# LEDRing.net
KiCad netlist of a schematic drawn in Altium Designer
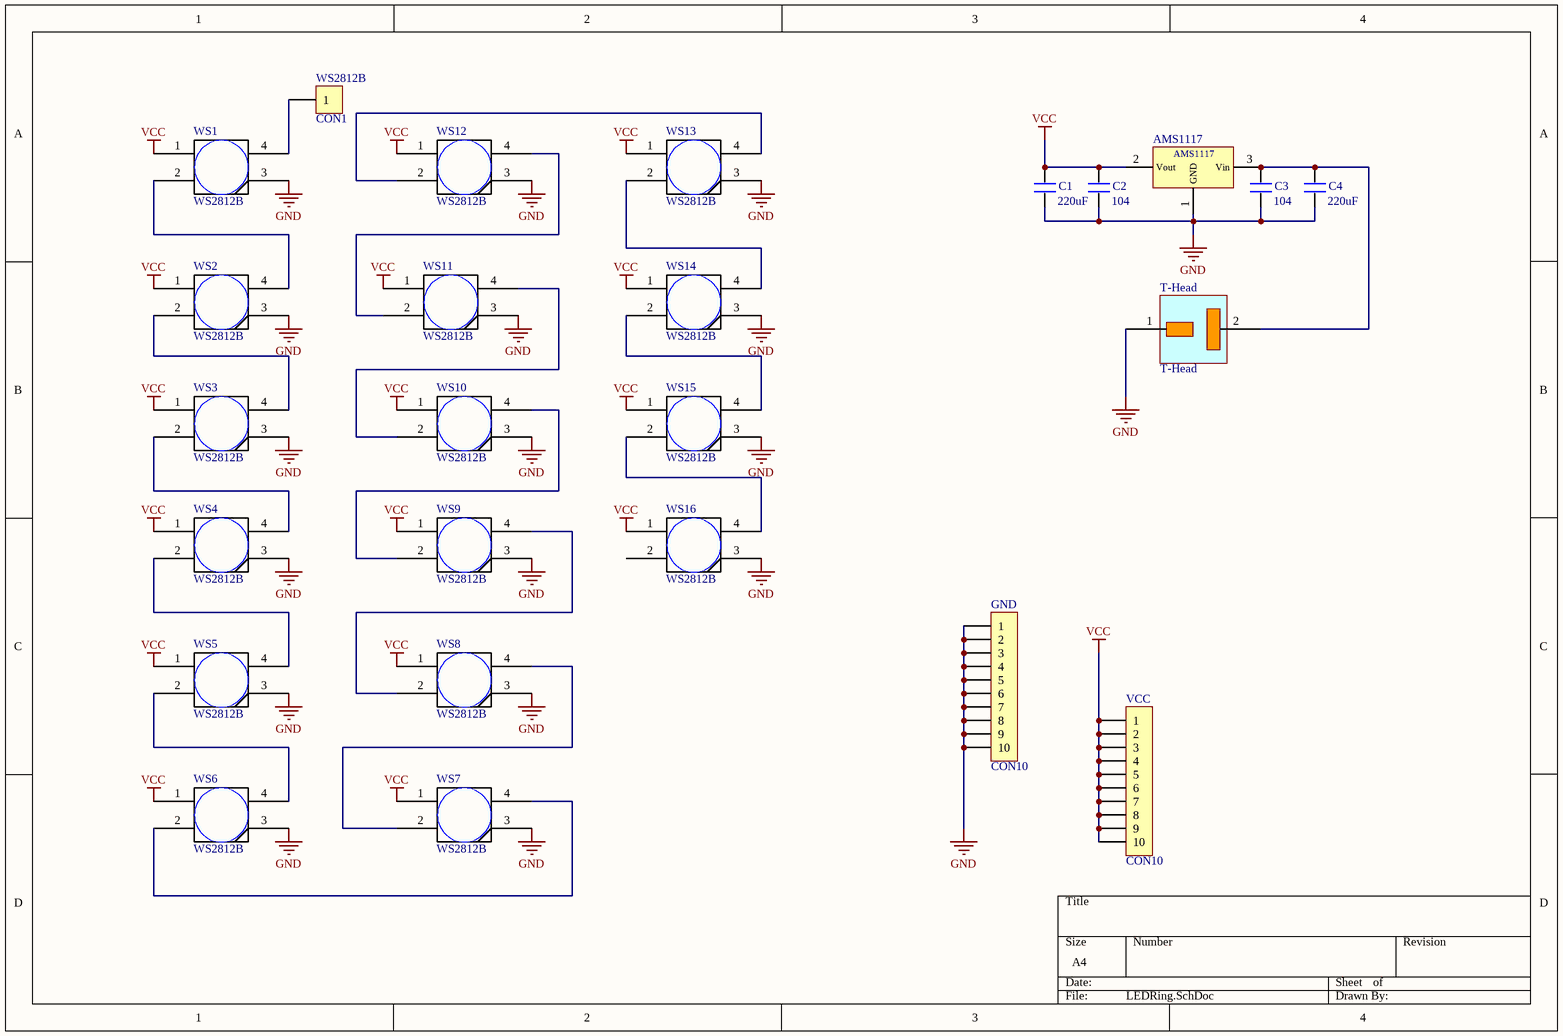
[diagram p0: LEDRing.SchDoc]

(export (version "E")
  (design (tool "Eeschema 10.0.6"))
  (components
    (comp (ref "AMS1117")
      (value "AMS1117")
      (footprint "AMS1117-3.3")
      (libsource (lib "WS2812") (part "AMS1117"))
    )
    (comp (ref "C1") (value "220uF") (footprint "0805") (libsource (lib "MiniFly V1.32") (part "C")))
    (comp (ref "C2") (value "104") (footprint "0805") (libsource (lib "MiniFly V1.32") (part "C")))
    (comp (ref "C3") (value "104") (footprint "0805") (libsource (lib "MiniFly V1.32") (part "C")))
    (comp (ref "C4") (value "220uF") (footprint "0805") (libsource (lib "MiniFly V1.32") (part "C")))
    (comp (ref "GND") (value "CON10") (footprint "HDR1X10") (libsource (lib "常用元件库") (part "CON10")))
    (comp (ref "T-Head") (value "T-Head") (footprint "T_head") (libsource (lib "WS2812") (part "T-Head")))
    (comp (ref "VCC") (value "CON10") (footprint "HDR1X10") (libsource (lib "常用元件库") (part "CON10")))
    (comp (ref "WS1") (value "WS2812B") (footprint "WS2812B") (libsource (lib "WS2812") (part "Component_1")))
    (comp (ref "WS2") (value "WS2812B") (footprint "WS2812B") (libsource (lib "WS2812") (part "Component_1")))
    (comp (ref "WS3") (value "WS2812B") (footprint "WS2812B") (libsource (lib "WS2812") (part "Component_1")))
    (comp (ref "WS4") (value "WS2812B") (footprint "WS2812B") (libsource (lib "WS2812") (part "Component_1")))
    (comp (ref "WS5") (value "WS2812B") (footprint "WS2812B") (libsource (lib "WS2812") (part "Component_1")))
    (comp (ref "WS6") (value "WS2812B") (footprint "WS2812B") (libsource (lib "WS2812") (part "Component_1")))
    (comp (ref "WS7") (value "WS2812B") (footprint "WS2812B") (libsource (lib "WS2812") (part "Component_1")))
    (comp (ref "WS8") (value "WS2812B") (footprint "WS2812B") (libsource (lib "WS2812") (part "Component_1")))
    (comp (ref "WS9") (value "WS2812B") (footprint "WS2812B") (libsource (lib "WS2812") (part "Component_1")))
    (comp (ref "WS10")
      (value "WS2812B")
      (footprint "WS2812B")
      (libsource (lib "WS2812") (part "Component_1"))
    )
    (comp (ref "WS11")
      (value "WS2812B")
      (footprint "WS2812B")
      (libsource (lib "WS2812") (part "Component_1"))
    )
    (comp (ref "WS12")
      (value "WS2812B")
      (footprint "WS2812B")
      (libsource (lib "WS2812") (part "Component_1"))
    )
    (comp (ref "WS13")
      (value "WS2812B")
      (footprint "WS2812B")
      (libsource (lib "WS2812") (part "Component_1"))
    )
    (comp (ref "WS14")
      (value "WS2812B")
      (footprint "WS2812B")
      (libsource (lib "WS2812") (part "Component_1"))
    )
    (comp (ref "WS15")
      (value "WS2812B")
      (footprint "WS2812B")
      (libsource (lib "WS2812") (part "Component_1"))
    )
    (comp (ref "WS16")
      (value "WS2812B")
      (footprint "WS2812B")
      (libsource (lib "WS2812") (part "Component_1"))
    )
    (comp (ref "WS2812B") (value "CON1") (footprint "PIN1") (libsource (lib "常用元件库") (part "CON1")))
  )
  (nets
    (net (code "1") (name "GND") (class "Default")
      (node (ref "AMS1117") (pin "1") (pinfunction "GND_1") (pintype "passive"))
      (node (ref "C1") (pin "1") (pintype "passive"))
      (node (ref "C2") (pin "1") (pintype "passive"))
      (node (ref "C3") (pin "1") (pintype "passive"))
      (node (ref "C4") (pin "1") (pintype "passive"))
      (node (ref "GND") (pin "1") (pinfunction "1_1") (pintype "passive"))
      (node (ref "GND") (pin "10") (pinfunction "10_10") (pintype "passive"))
      (node (ref "GND") (pin "2") (pinfunction "2_2") (pintype "passive"))
      (node (ref "GND") (pin "3") (pinfunction "3_3") (pintype "passive"))
      (node (ref "GND") (pin "4") (pinfunction "4_4") (pintype "passive"))
      (node (ref "GND") (pin "5") (pinfunction "5_5") (pintype "passive"))
      (node (ref "GND") (pin "6") (pinfunction "6_6") (pintype "passive"))
      (node (ref "GND") (pin "7") (pinfunction "7_7") (pintype "passive"))
      (node (ref "GND") (pin "8") (pinfunction "8_8") (pintype "passive"))
      (node (ref "GND") (pin "9") (pinfunction "9_9") (pintype "passive"))
      (node (ref "T-Head") (pin "1") (pinfunction "GND_1") (pintype "passive"))
      (node (ref "WS1") (pin "3") (pinfunction "GND_3") (pintype "passive"))
      (node (ref "WS10") (pin "3") (pinfunction "GND_3") (pintype "passive"))
      (node (ref "WS11") (pin "3") (pinfunction "GND_3") (pintype "passive"))
      (node (ref "WS12") (pin "3") (pinfunction "GND_3") (pintype "passive"))
      (node (ref "WS13") (pin "3") (pinfunction "GND_3") (pintype "passive"))
      (node (ref "WS14") (pin "3") (pinfunction "GND_3") (pintype "passive"))
      (node (ref "WS15") (pin "3") (pinfunction "GND_3") (pintype "passive"))
      (node (ref "WS16") (pin "3") (pinfunction "GND_3") (pintype "passive"))
      (node (ref "WS2") (pin "3") (pinfunction "GND_3") (pintype "passive"))
      (node (ref "WS3") (pin "3") (pinfunction "GND_3") (pintype "passive"))
      (node (ref "WS4") (pin "3") (pinfunction "GND_3") (pintype "passive"))
      (node (ref "WS5") (pin "3") (pinfunction "GND_3") (pintype "passive"))
      (node (ref "WS6") (pin "3") (pinfunction "GND_3") (pintype "passive"))
      (node (ref "WS7") (pin "3") (pinfunction "GND_3") (pintype "passive"))
      (node (ref "WS8") (pin "3") (pinfunction "GND_3") (pintype "passive"))
      (node (ref "WS9") (pin "3") (pinfunction "GND_3") (pintype "passive"))
    )
    (net (code "2") (name "Net-(AMS1117-Vin)") (class "Default")
      (node (ref "AMS1117") (pin "3") (pinfunction "Vin_3") (pintype "passive"))
      (node (ref "C3") (pin "2") (pintype "passive"))
      (node (ref "C4") (pin "2") (pintype "passive"))
      (node (ref "T-Head") (pin "2") (pinfunction "VCC_2") (pintype "passive"))
    )
    (net (code "3") (name "Net-(WS1-DIN)") (class "Default")
      (node (ref "WS1") (pin "4") (pinfunction "DIN_4") (pintype "passive"))
      (node (ref "WS2812B") (pin "1") (pinfunction "1_1") (pintype "passive"))
    )
    (net (code "4") (name "Net-(WS1-DOUT)") (class "Default")
      (node (ref "WS1") (pin "2") (pinfunction "DOUT_2") (pintype "passive"))
      (node (ref "WS2") (pin "4") (pinfunction "DIN_4") (pintype "passive"))
    )
    (net (code "5") (name "Net-(WS2-DOUT)") (class "Default")
      (node (ref "WS2") (pin "2") (pinfunction "DOUT_2") (pintype "passive"))
      (node (ref "WS3") (pin "4") (pinfunction "DIN_4") (pintype "passive"))
    )
    (net (code "6") (name "Net-(WS3-DOUT)") (class "Default")
      (node (ref "WS3") (pin "2") (pinfunction "DOUT_2") (pintype "passive"))
      (node (ref "WS4") (pin "4") (pinfunction "DIN_4") (pintype "passive"))
    )
    (net (code "7") (name "Net-(WS4-DOUT)") (class "Default")
      (node (ref "WS4") (pin "2") (pinfunction "DOUT_2") (pintype "passive"))
      (node (ref "WS5") (pin "4") (pinfunction "DIN_4") (pintype "passive"))
    )
    (net (code "8") (name "Net-(WS5-DOUT)") (class "Default")
      (node (ref "WS5") (pin "2") (pinfunction "DOUT_2") (pintype "passive"))
      (node (ref "WS6") (pin "4") (pinfunction "DIN_4") (pintype "passive"))
    )
    (net (code "9") (name "Net-(WS6-DOUT)") (class "Default")
      (node (ref "WS6") (pin "2") (pinfunction "DOUT_2") (pintype "passive"))
      (node (ref "WS7") (pin "4") (pinfunction "DIN_4") (pintype "passive"))
    )
    (net (code "10") (name "Net-(WS7-DOUT)") (class "Default")
      (node (ref "WS7") (pin "2") (pinfunction "DOUT_2") (pintype "passive"))
      (node (ref "WS8") (pin "4") (pinfunction "DIN_4") (pintype "passive"))
    )
    (net (code "11") (name "Net-(WS8-DOUT)") (class "Default")
      (node (ref "WS8") (pin "2") (pinfunction "DOUT_2") (pintype "passive"))
      (node (ref "WS9") (pin "4") (pinfunction "DIN_4") (pintype "passive"))
    )
    (net (code "12") (name "Net-(WS10-DIN)") (class "Default")
      (node (ref "WS10") (pin "4") (pinfunction "DIN_4") (pintype "passive"))
      (node (ref "WS9") (pin "2") (pinfunction "DOUT_2") (pintype "passive"))
    )
    (net (code "13") (name "Net-(WS10-DOUT)") (class "Default")
      (node (ref "WS10") (pin "2") (pinfunction "DOUT_2") (pintype "passive"))
      (node (ref "WS11") (pin "4") (pinfunction "DIN_4") (pintype "passive"))
    )
    (net (code "14") (name "Net-(WS11-DOUT)") (class "Default")
      (node (ref "WS11") (pin "2") (pinfunction "DOUT_2") (pintype "passive"))
      (node (ref "WS12") (pin "4") (pinfunction "DIN_4") (pintype "passive"))
    )
    (net (code "15") (name "Net-(WS12-DOUT)") (class "Default")
      (node (ref "WS12") (pin "2") (pinfunction "DOUT_2") (pintype "passive"))
      (node (ref "WS13") (pin "4") (pinfunction "DIN_4") (pintype "passive"))
    )
    (net (code "16") (name "Net-(WS13-DOUT)") (class "Default")
      (node (ref "WS13") (pin "2") (pinfunction "DOUT_2") (pintype "passive"))
      (node (ref "WS14") (pin "4") (pinfunction "DIN_4") (pintype "passive"))
    )
    (net (code "17") (name "Net-(WS14-DOUT)") (class "Default")
      (node (ref "WS14") (pin "2") (pinfunction "DOUT_2") (pintype "passive"))
      (node (ref "WS15") (pin "4") (pinfunction "DIN_4") (pintype "passive"))
    )
    (net (code "18") (name "Net-(WS15-DOUT)") (class "Default")
      (node (ref "WS15") (pin "2") (pinfunction "DOUT_2") (pintype "passive"))
      (node (ref "WS16") (pin "4") (pinfunction "DIN_4") (pintype "passive"))
    )
    (net (code "19") (name "VCC") (class "Default")
      (node (ref "AMS1117") (pin "2") (pinfunction "Vout_2") (pintype "passive"))
      (node (ref "C1") (pin "2") (pintype "passive"))
      (node (ref "C2") (pin "2") (pintype "passive"))
      (node (ref "VCC") (pin "1") (pinfunction "1_1") (pintype "passive"))
      (node (ref "VCC") (pin "10") (pinfunction "10_10") (pintype "passive"))
      (node (ref "VCC") (pin "2") (pinfunction "2_2") (pintype "passive"))
      (node (ref "VCC") (pin "3") (pinfunction "3_3") (pintype "passive"))
      (node (ref "VCC") (pin "4") (pinfunction "4_4") (pintype "passive"))
      (node (ref "VCC") (pin "5") (pinfunction "5_5") (pintype "passive"))
      (node (ref "VCC") (pin "6") (pinfunction "6_6") (pintype "passive"))
      (node (ref "VCC") (pin "7") (pinfunction "7_7") (pintype "passive"))
      (node (ref "VCC") (pin "8") (pinfunction "8_8") (pintype "passive"))
      (node (ref "VCC") (pin "9") (pinfunction "9_9") (pintype "passive"))
      (node (ref "WS1") (pin "1") (pinfunction "VDD_1") (pintype "passive"))
      (node (ref "WS10") (pin "1") (pinfunction "VDD_1") (pintype "passive"))
      (node (ref "WS11") (pin "1") (pinfunction "VDD_1") (pintype "passive"))
      (node (ref "WS12") (pin "1") (pinfunction "VDD_1") (pintype "passive"))
      (node (ref "WS13") (pin "1") (pinfunction "VDD_1") (pintype "passive"))
      (node (ref "WS14") (pin "1") (pinfunction "VDD_1") (pintype "passive"))
      (node (ref "WS15") (pin "1") (pinfunction "VDD_1") (pintype "passive"))
      (node (ref "WS16") (pin "1") (pinfunction "VDD_1") (pintype "passive"))
      (node (ref "WS2") (pin "1") (pinfunction "VDD_1") (pintype "passive"))
      (node (ref "WS3") (pin "1") (pinfunction "VDD_1") (pintype "passive"))
      (node (ref "WS4") (pin "1") (pinfunction "VDD_1") (pintype "passive"))
      (node (ref "WS5") (pin "1") (pinfunction "VDD_1") (pintype "passive"))
      (node (ref "WS6") (pin "1") (pinfunction "VDD_1") (pintype "passive"))
      (node (ref "WS7") (pin "1") (pinfunction "VDD_1") (pintype "passive"))
      (node (ref "WS8") (pin "1") (pinfunction "VDD_1") (pintype "passive"))
      (node (ref "WS9") (pin "1") (pinfunction "VDD_1") (pintype "passive"))
    )
    (net (code "20") (name "unconnected-(WS16-DOUT-Pad2)") (class "Default")
      (node (ref "WS16") (pin "2") (pinfunction "DOUT_2") (pintype "passive"))
    )
  )
)
